# Power.net
KiCad netlist of a schematic drawn in Altium Designer
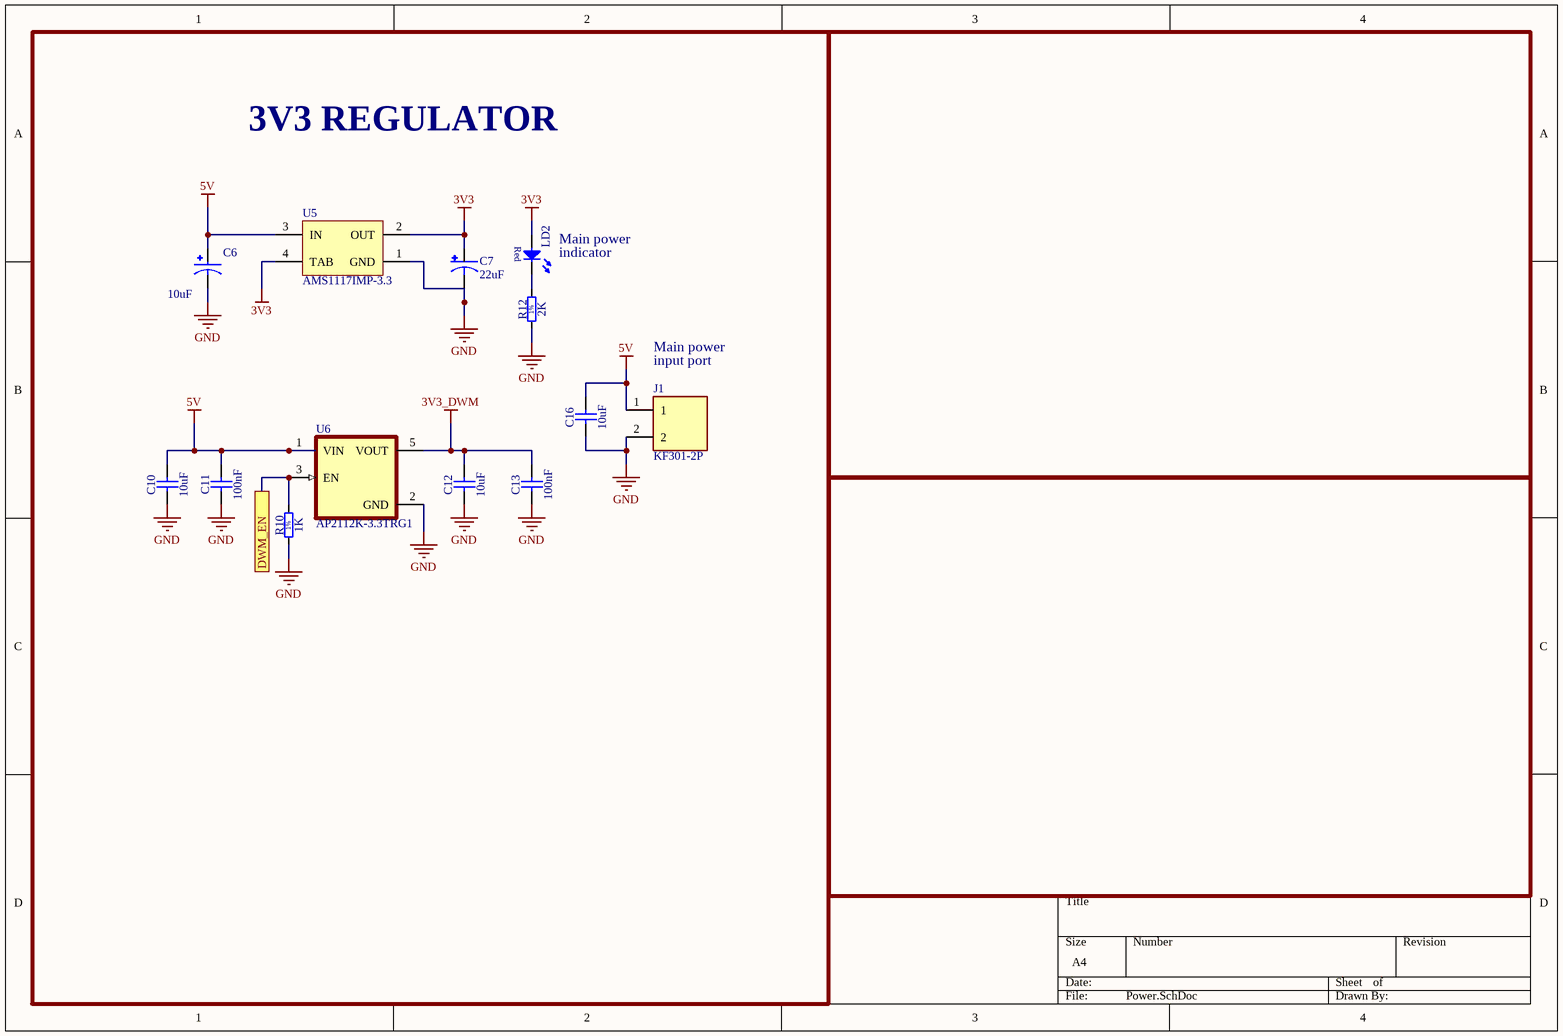
[diagram p0: Power.SchDoc]

(export (version "E")
  (design (tool "Eeschema 10.0.6"))
  (components
    (comp (ref "C6")
      (value "10uF")
      (footprint "CAPMP3216X180N")
      (description "10 ÂµF Molded Tantalum Polymer Capacitor 10 V 1206 (3216 Metric) 80mOhm @ 100kHz")
      (fields (field (name "MF") "KEMET") (field (name "MP") "T543A106K010ATW080"))
      (libsource (lib "T543A106K010ATW080") (part "T543A106K010ATW080"))
    )
    (comp (ref "C7")
      (value "22uF")
      (footprint "CAPMP3528X210N")
      (fields (field (name "MF") "AVX") (field (name "MP") "TPSB226K016R0600"))
      (libsource (lib "TPSB226K016R0600") (part "TPSB226K016R0600"))
    )
    (comp (ref "C10")
      (value "10uF")
      (footprint "0603C")
      (description "Non-polarised capacitor")
      (libsource (lib "Universal Acq") (part "Capacitor - non polarized"))
    )
    (comp (ref "C11")
      (value "100nF")
      (footprint "0603C")
      (description "Non-polarised capacitor")
      (libsource (lib "Universal Acq") (part "Capacitor - non polarized"))
    )
    (comp (ref "C12")
      (value "10uF")
      (footprint "0603C")
      (description "Non-polarised capacitor")
      (libsource (lib "Universal Acq") (part "Capacitor - non polarized"))
    )
    (comp (ref "C13")
      (value "100nF")
      (footprint "0603C")
      (description "Non-polarised capacitor")
      (libsource (lib "Universal Acq") (part "Capacitor - non polarized"))
    )
    (comp (ref "C16")
      (value "10uF")
      (footprint "0603C")
      (description "Non-polarised capacitor")
      (libsource (lib "Universal Acq") (part "Capacitor - non polarized"))
    )
    (comp (ref "J1")
      (value "KF301-2P")
      (footprint "HANDSON_KF301-2P")
      (description "2 Pin Terminal Block 5mm Pitch")
      (fields (field (name "MF") "Handson Technology"))
      (libsource (lib "KF301-2P") (part "KF301-2P"))
    )
    (comp (ref "LD2")
      (value "~")
      (footprint "0603 LED")
      (description "LED Red 1C 2A")
      (libsource (lib "Universal Acq") (part "LED Red 1C 2A"))
    )
    (comp (ref "R10")
      (value "1K")
      (footprint "0603R")
      (description "Resistor - 1%")
      (libsource (lib "Universal Acq") (part "Resistor - 1%_1"))
    )
    (comp (ref "R12")
      (value "2K")
      (footprint "0603R")
      (description "Resistor - 1%")
      (libsource (lib "Universal Acq") (part "Resistor - 1%_1"))
    )
    (comp (ref "U5")
      (value "AMS1117IMP-3.3")
      (footprint "VREG_LM1117IMP-3.3/NOPB")
      (description "800mA Low-Dropout Linear Regulator, 4-pin SOT-223")
      (fields
        (field (name "PARTNUMBER") "LM1117IMP-3.3")
        (field (name "MANUFACTURER") "National Semiconductor")
      )
      (libsource (lib "National Semiconductor LDO") (part "LM1117IMP-3.3"))
    )
    (comp (ref "U6")
      (value "AP2112K-3.3TRG1")
      (footprint "SOT95P285X140-5N")
      (description "Linear Voltage Regulator IC Positive Fixed 1 Output 600mA SOT-25")
      (fields (field (name "MF") "Diodes Inc."))
      (libsource (lib "AP2112K-3.3TRG1") (part "AP2112K-3.3TRG1"))
    )
  )
  (nets
    (net (code "1") (name "/DWM_EN") (class "Default")
      (node (ref "R10") (pin "2") (pinfunction "2_2") (pintype "passive"))
      (node (ref "U6") (pin "3") (pinfunction "EN_3") (pintype "input"))
    )
    (net (code "2") (name "3V3") (class "Default")
      (node (ref "C7") (pin "1") (pinfunction "1_1") (pintype "passive"))
      (node (ref "LD2") (pin "2") (pinfunction "A_2") (pintype "passive"))
      (node (ref "U5") (pin "2") (pinfunction "OUT_2") (pintype "power_in"))
      (node (ref "U5") (pin "4") (pinfunction "TAB_4") (pintype "power_in"))
    )
    (net (code "3") (name "3V3_DWM") (class "Default")
      (node (ref "C12") (pin "2") (pinfunction "2_2") (pintype "passive"))
      (node (ref "C13") (pin "2") (pinfunction "2_2") (pintype "passive"))
      (node (ref "U6") (pin "5") (pinfunction "VOUT_5") (pintype "power_in"))
    )
    (net (code "4") (name "5V") (class "Default")
      (node (ref "C10") (pin "2") (pinfunction "2_2") (pintype "passive"))
      (node (ref "C11") (pin "2") (pinfunction "2_2") (pintype "passive"))
      (node (ref "C16") (pin "2") (pinfunction "2_2") (pintype "passive"))
      (node (ref "C6") (pin "1") (pinfunction "1_1") (pintype "passive"))
      (node (ref "J1") (pin "1") (pinfunction "1_1") (pintype "passive"))
      (node (ref "U5") (pin "3") (pinfunction "IN_3") (pintype "power_in"))
      (node (ref "U6") (pin "1") (pinfunction "VIN_1") (pintype "power_in"))
    )
    (net (code "5") (name "GND") (class "Default")
      (node (ref "C10") (pin "1") (pinfunction "1_1") (pintype "passive"))
      (node (ref "C11") (pin "1") (pinfunction "1_1") (pintype "passive"))
      (node (ref "C12") (pin "1") (pinfunction "1_1") (pintype "passive"))
      (node (ref "C13") (pin "1") (pinfunction "1_1") (pintype "passive"))
      (node (ref "C16") (pin "1") (pinfunction "1_1") (pintype "passive"))
      (node (ref "C6") (pin "2") (pinfunction "2_2") (pintype "passive"))
      (node (ref "C7") (pin "2") (pinfunction "2_2") (pintype "passive"))
      (node (ref "J1") (pin "2") (pinfunction "2_2") (pintype "passive"))
      (node (ref "R10") (pin "1") (pinfunction "1_1") (pintype "passive"))
      (node (ref "R12") (pin "1") (pinfunction "1_1") (pintype "passive"))
      (node (ref "U5") (pin "1") (pinfunction "GND_1") (pintype "power_in"))
      (node (ref "U6") (pin "2") (pinfunction "GND_2") (pintype "power_in"))
    )
    (net (code "6") (name "Net-(LD2-C)") (class "Default")
      (node (ref "LD2") (pin "1") (pinfunction "C_1") (pintype "passive"))
      (node (ref "R12") (pin "2") (pinfunction "2_2") (pintype "passive"))
    )
  )
)
